# Servo_Motor.net
KiCad netlist of a schematic drawn in Altium Designer
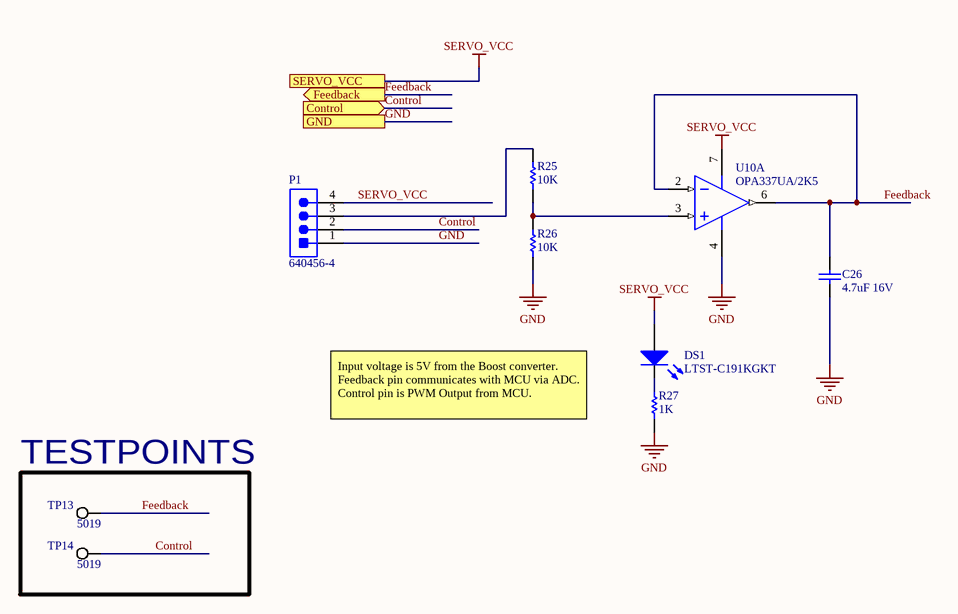
[diagram p0: Servo Motor.SchDoc]

(export (version "E")
  (design (tool "Eeschema 10.0.6"))
  (components
    (comp (ref "C26")
      (value "4.7uF 16V")
      (footprint "CAPC0805(2012)145_N")
      (description "CAP 4.7uF 16V ±10% 0805 (2012 Metric) Thickness 1.45mm SMD")
      (fields (field (name "TOLERANCE") "Â±10%"))
      (libsource (lib "Altium Content Vault") (part "CAP"))
    )
    (comp (ref "DS1")
      (value "LTST-C191KGKT")
      (footprint "LITE-ON-LTST-C191KRKT-2_V")
      (description "Chip LED, Green, 574 nm, 40 pF, -55 to 85 degC, 2-Pin SMD, RoHS, Tape and Reel")
      (fields (field (name "MANUFACTURER") "Lite-On"))
      (libsource (lib "Altium Content Vault") (part "LED-AK-2"))
    )
    (comp (ref "P1")
      (value "640456-4")
      (footprint "TECO-640456-4")
      (description "Male Header, Pitch 2.54 mm, 1 x 4 Position, Height 10.03 mm, Tail Length 3.56 mm, RoHS, Bulk")
      (fields (field (name "MANUFACTURER") "TE Connectivity"))
      (libsource (lib "Altium Content Vault") (part "CN-1P-M-R4"))
    )
    (comp (ref "R25")
      (value "10K")
      (footprint "RESC2013X70X40ML20T20")
      (fields (field (name "MANUFACTURER") "Panasonic") (field (name "PART NUMBER") "ERJ-6ENF1002V"))
      (libsource (lib "Altium Content Vault") (part "RES"))
    )
    (comp (ref "R26")
      (value "10K")
      (footprint "RESC2013X70X40ML20T20")
      (fields (field (name "MANUFACTURER") "Panasonic") (field (name "PART NUMBER") "ERJ-6ENF1002V"))
      (libsource (lib "Altium Content Vault") (part "RES"))
    )
    (comp (ref "R27")
      (value "1K")
      (footprint "RESC0603(1608)_M")
      (description "1K 0.1W 1% 0603 (1608 Metric)  SMD")
      (fields (field (name "TOLERANCE") "1 %") (field (name "POWER") "0.1 W"))
      (libsource (lib "Altium Content Vault") (part "RES"))
    )
    (comp (ref "TP13")
      (value "5019")
      (footprint "KSTN-5019_V")
      (description "Test Point, 1 Position SMD, RoHS, Tape and Reel")
      (libsource (lib "Altium Content Vault") (part "TESTPOINT_WHITE"))
    )
    (comp (ref "TP14")
      (value "5019")
      (footprint "KSTN-5019_V")
      (description "Test Point, 1 Position SMD, RoHS, Tape and Reel")
      (libsource (lib "Altium Content Vault") (part "TESTPOINT_WHITE"))
    )
    (comp (ref "U10")
      (value "OPA337UA/2K5")
      (footprint "D0008A_N")
      (fields (field (name "MANUFACTURER") "Texas Instruments"))
      (libsource (lib "Altium Content Vault") (part "TI-OPA-8_1"))
    )
  )
  (nets
    (net (code "1") (name "/Control") (class "Default")
      (node (ref "P1") (pin "2") (pinfunction "2_2") (pintype "passive"))
      (node (ref "TP14") (pin "1") (pinfunction "1_1") (pintype "passive"))
    )
    (net (code "2") (name "/Feedback") (class "Default")
      (node (ref "C26") (pin "2") (pinfunction "2_2") (pintype "passive"))
      (node (ref "TP13") (pin "1") (pinfunction "1_1") (pintype "passive"))
      (node (ref "U10") (pin "2") (pinfunction "IN-_2") (pintype "input"))
      (node (ref "U10") (pin "6") (pinfunction "OUT_6") (pintype "output"))
    )
    (net (code "3") (name "GND") (class "Default")
      (node (ref "C26") (pin "1") (pinfunction "1_1") (pintype "passive"))
      (node (ref "P1") (pin "1") (pinfunction "1_1") (pintype "passive"))
      (node (ref "R26") (pin "1") (pinfunction "1_1") (pintype "passive"))
      (node (ref "R27") (pin "2") (pinfunction "2_2") (pintype "passive"))
      (node (ref "U10") (pin "4") (pinfunction "V-_4") (pintype "power_in"))
    )
    (net (code "4") (name "Net-(DS1-K)") (class "Default")
      (node (ref "DS1") (pin "2") (pinfunction "K_2") (pintype "passive"))
      (node (ref "R27") (pin "1") (pinfunction "1_1") (pintype "passive"))
    )
    (net (code "5") (name "Net-(P1-Pad3)") (class "Default")
      (node (ref "P1") (pin "3") (pinfunction "3_3") (pintype "passive"))
      (node (ref "R25") (pin "2") (pinfunction "2_2") (pintype "passive"))
    )
    (net (code "6") (name "Net-(U10A-IN+)") (class "Default")
      (node (ref "R25") (pin "1") (pinfunction "1_1") (pintype "passive"))
      (node (ref "R26") (pin "2") (pinfunction "2_2") (pintype "passive"))
      (node (ref "U10") (pin "3") (pinfunction "IN+_3") (pintype "input"))
    )
    (net (code "7") (name "SERVO_VCC") (class "Default")
      (node (ref "DS1") (pin "1") (pinfunction "A_1") (pintype "passive"))
      (node (ref "P1") (pin "4") (pinfunction "4_4") (pintype "passive"))
      (node (ref "U10") (pin "7") (pinfunction "V+_7") (pintype "power_in"))
    )
  )
)
